# stm32f4discovery-daugherboard-v1-THT.net
KiCad netlist of a schematic drawn in EAGLE
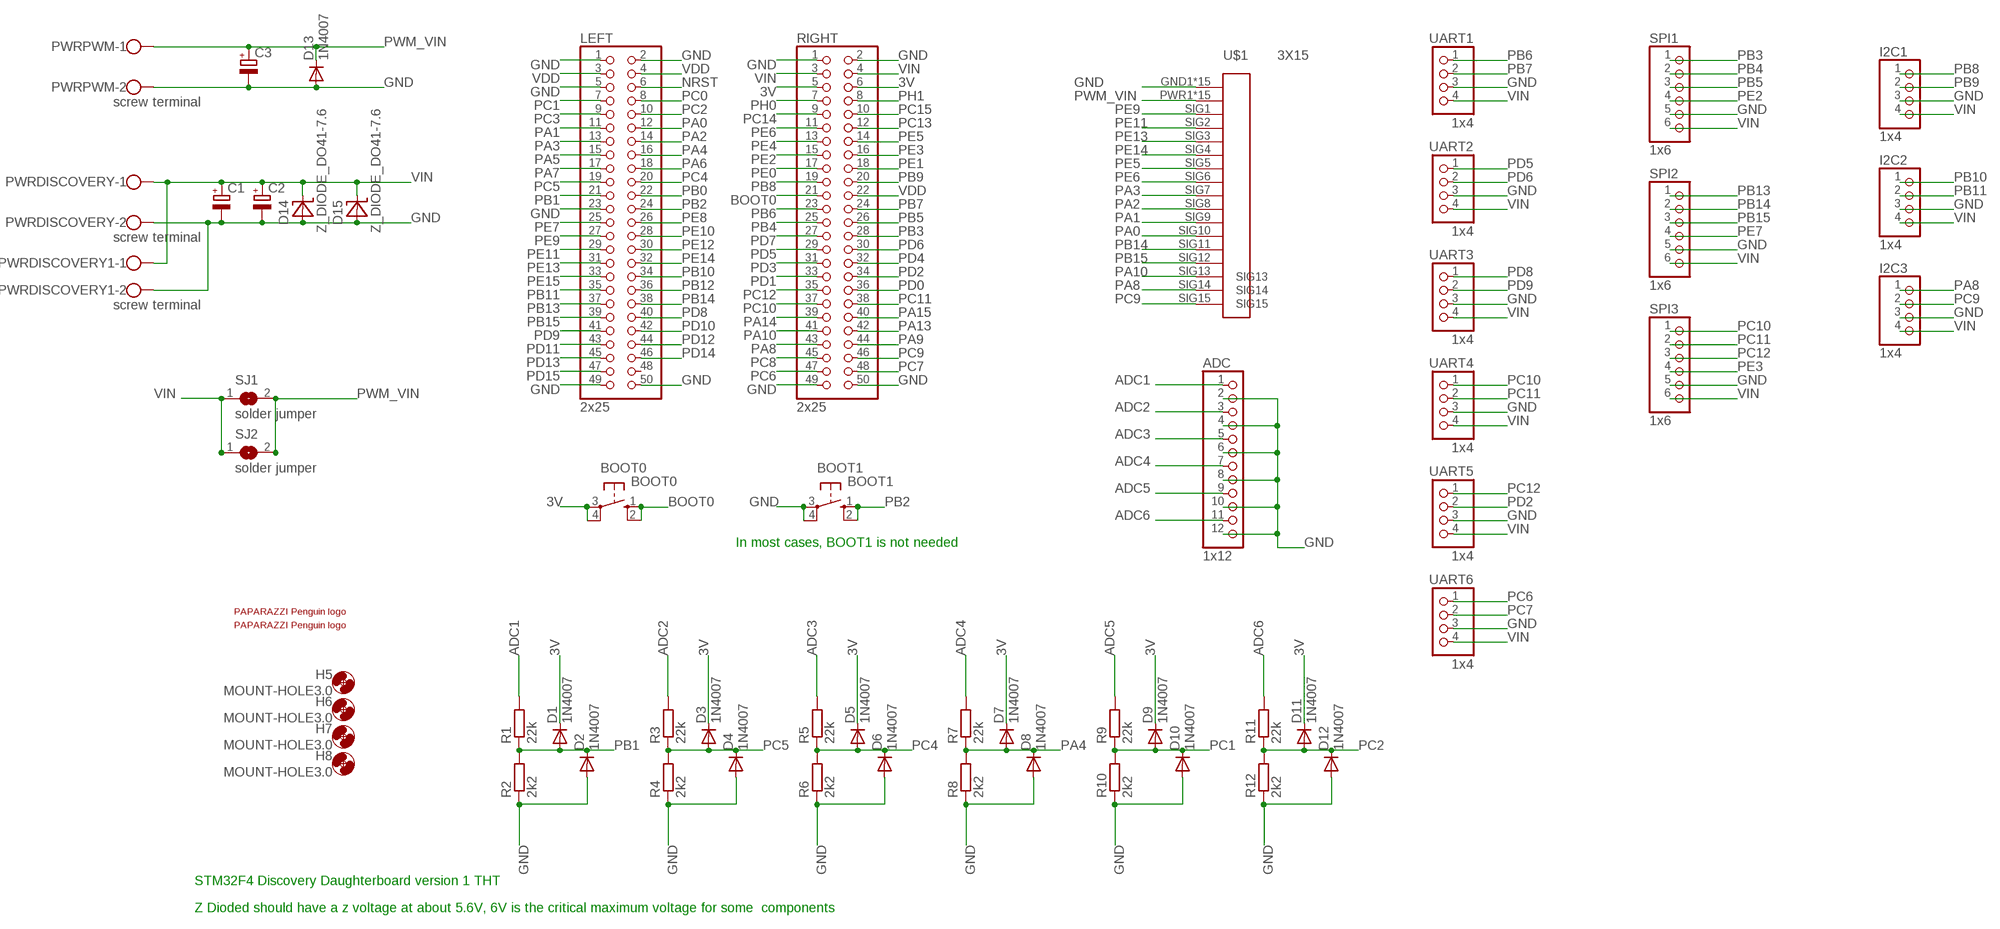
[diagram p0: schematic, sheet 1]

(export (version "E")
  (design (tool "Eeschema 10.0.6"))
  (components
    (comp (ref "ADC")
      (value "1x12")
      (footprint "eagle-import:1X12_90")
      (libsource (lib "eagle-import") (part "PINHD-1X12/90"))
    )
    (comp (ref "BOOT0")
      (value "BOOT0")
      (footprint "eagle-import:B3F-10XX")
      (fields (field (name "MPN") "B3F-1000"))
      (libsource (lib "eagle-import") (part "10-XX"))
    )
    (comp (ref "BOOT1")
      (value "BOOT1")
      (footprint "eagle-import:B3F-10XX")
      (fields (field (name "MPN") "B3F-1000"))
      (libsource (lib "eagle-import") (part "10-XX"))
    )
    (comp (ref "C1")
      (value "CPOL-EUE5-8.5")
      (footprint "eagle-import:E5-8,5")
      (libsource (lib "eagle-import") (part "CPOL-EUE5-8.5"))
    )
    (comp (ref "C2")
      (value "CPOL-EUE5-8.5")
      (footprint "eagle-import:E5-8,5")
      (libsource (lib "eagle-import") (part "CPOL-EUE5-8.5"))
    )
    (comp (ref "C3")
      (value "CPOL-EUE5-8.5")
      (footprint "eagle-import:E5-8,5")
      (libsource (lib "eagle-import") (part "CPOL-EUE5-8.5"))
    )
    (comp (ref "D1")
      (value "1N4007")
      (footprint "eagle-import:DO41-7.6_2")
      (libsource (lib "eagle-import") (part "1N4007"))
    )
    (comp (ref "D2")
      (value "1N4007")
      (footprint "eagle-import:DO41-7.6_2")
      (libsource (lib "eagle-import") (part "1N4007"))
    )
    (comp (ref "D3")
      (value "1N4007")
      (footprint "eagle-import:DO41-7.6_2")
      (libsource (lib "eagle-import") (part "1N4007"))
    )
    (comp (ref "D4")
      (value "1N4007")
      (footprint "eagle-import:DO41-7.6_2")
      (libsource (lib "eagle-import") (part "1N4007"))
    )
    (comp (ref "D5")
      (value "1N4007")
      (footprint "eagle-import:DO41-7.6_2")
      (libsource (lib "eagle-import") (part "1N4007"))
    )
    (comp (ref "D6")
      (value "1N4007")
      (footprint "eagle-import:DO41-7.6_2")
      (libsource (lib "eagle-import") (part "1N4007"))
    )
    (comp (ref "D7")
      (value "1N4007")
      (footprint "eagle-import:DO41-7.6_2")
      (libsource (lib "eagle-import") (part "1N4007"))
    )
    (comp (ref "D8")
      (value "1N4007")
      (footprint "eagle-import:DO41-7.6_2")
      (libsource (lib "eagle-import") (part "1N4007"))
    )
    (comp (ref "D9")
      (value "1N4007")
      (footprint "eagle-import:DO41-7.6_2")
      (libsource (lib "eagle-import") (part "1N4007"))
    )
    (comp (ref "D10")
      (value "1N4007")
      (footprint "eagle-import:DO41-7.6_2")
      (libsource (lib "eagle-import") (part "1N4007"))
    )
    (comp (ref "D11")
      (value "1N4007")
      (footprint "eagle-import:DO41-7.6_2")
      (libsource (lib "eagle-import") (part "1N4007"))
    )
    (comp (ref "D12")
      (value "1N4007")
      (footprint "eagle-import:DO41-7.6_2")
      (libsource (lib "eagle-import") (part "1N4007"))
    )
    (comp (ref "D13")
      (value "1N4007")
      (footprint "eagle-import:DO41-7.6_2")
      (libsource (lib "eagle-import") (part "1N4007"))
    )
    (comp (ref "D14")
      (value "Z_DIODE_DO41-7.6")
      (footprint "eagle-import:DO41-7.6_Z")
      (libsource (lib "eagle-import") (part "Z_DIODE_DO41-7.6"))
    )
    (comp (ref "D15")
      (value "Z_DIODE_DO41-7.6")
      (footprint "eagle-import:DO41-7.6_Z")
      (libsource (lib "eagle-import") (part "Z_DIODE_DO41-7.6"))
    )
    (comp (ref "H5")
      (value "MOUNT-HOLE3.0")
      (footprint "eagle-import:3,0")
      (libsource (lib "eagle-import") (part "MOUNT-HOLE3.0"))
    )
    (comp (ref "H6")
      (value "MOUNT-HOLE3.0")
      (footprint "eagle-import:3,0")
      (libsource (lib "eagle-import") (part "MOUNT-HOLE3.0"))
    )
    (comp (ref "H7")
      (value "MOUNT-HOLE3.0")
      (footprint "eagle-import:3,0")
      (libsource (lib "eagle-import") (part "MOUNT-HOLE3.0"))
    )
    (comp (ref "H8")
      (value "MOUNT-HOLE3.0")
      (footprint "eagle-import:3,0")
      (libsource (lib "eagle-import") (part "MOUNT-HOLE3.0"))
    )
    (comp (ref "I2C1")
      (value "1x4")
      (footprint "eagle-import:1X04_90")
      (libsource (lib "eagle-import") (part "PINHD-1X4/90"))
    )
    (comp (ref "I2C2")
      (value "1x4")
      (footprint "eagle-import:1X04_90")
      (libsource (lib "eagle-import") (part "PINHD-1X4/90"))
    )
    (comp (ref "I2C3")
      (value "1x4")
      (footprint "eagle-import:1X04_90")
      (libsource (lib "eagle-import") (part "PINHD-1X4/90"))
    )
    (comp (ref "LEFT")
      (value "2x25")
      (footprint "eagle-import:2X25")
      (libsource (lib "eagle-import") (part "PINHD-2X25"))
    )
    (comp (ref "PWRDISCOVERY")
      (value "screw terminal")
      (footprint "eagle-import:W237-102")
      (fields (field (name "MPN") "237-102"))
      (libsource (lib "eagle-import") (part "W237-102"))
    )
    (comp (ref "PWRDISCOVERY1")
      (value "screw terminal")
      (footprint "eagle-import:W237-102")
      (fields
        (field (name "MPN") "237-102")
        (field (name "MPN_1") "237-102")
        (field (name "OC_FARNELL") "unknown")
        (field (name "OC_NEWARK") "70K9898")
      )
      (libsource (lib "eagle-import") (part "W237-102"))
    )
    (comp (ref "PWRPWM")
      (value "screw terminal")
      (footprint "eagle-import:W237-102")
      (fields (field (name "MPN") "237-102"))
      (libsource (lib "eagle-import") (part "W237-102"))
    )
    (comp (ref "R1")
      (value "22k")
      (footprint "eagle-import:0204_7")
      (libsource (lib "eagle-import") (part "R-EU_0204/7"))
    )
    (comp (ref "R2")
      (value "2k2")
      (footprint "eagle-import:0204_7")
      (libsource (lib "eagle-import") (part "R-EU_0204/7"))
    )
    (comp (ref "R3")
      (value "22k")
      (footprint "eagle-import:0204_7")
      (libsource (lib "eagle-import") (part "R-EU_0204/7"))
    )
    (comp (ref "R4")
      (value "2k2")
      (footprint "eagle-import:0204_7")
      (libsource (lib "eagle-import") (part "R-EU_0204/7"))
    )
    (comp (ref "R5")
      (value "22k")
      (footprint "eagle-import:0204_7")
      (libsource (lib "eagle-import") (part "R-EU_0204/7"))
    )
    (comp (ref "R6")
      (value "2k2")
      (footprint "eagle-import:0204_7")
      (libsource (lib "eagle-import") (part "R-EU_0204/7"))
    )
    (comp (ref "R7")
      (value "22k")
      (footprint "eagle-import:0204_7")
      (libsource (lib "eagle-import") (part "R-EU_0204/7"))
    )
    (comp (ref "R8")
      (value "2k2")
      (footprint "eagle-import:0204_7")
      (libsource (lib "eagle-import") (part "R-EU_0204/7"))
    )
    (comp (ref "R9")
      (value "22k")
      (footprint "eagle-import:0204_7")
      (libsource (lib "eagle-import") (part "R-EU_0204/7"))
    )
    (comp (ref "R10")
      (value "2k2")
      (footprint "eagle-import:0204_7")
      (libsource (lib "eagle-import") (part "R-EU_0204/7"))
    )
    (comp (ref "R11")
      (value "22k")
      (footprint "eagle-import:0204_7")
      (libsource (lib "eagle-import") (part "R-EU_0204/7"))
    )
    (comp (ref "R12")
      (value "2k2")
      (footprint "eagle-import:0204_7")
      (libsource (lib "eagle-import") (part "R-EU_0204/7"))
    )
    (comp (ref "RIGHT")
      (value "2x25")
      (footprint "eagle-import:2X25")
      (libsource (lib "eagle-import") (part "PINHD-2X25"))
    )
    (comp (ref "SJ1")
      (value "solder jumper")
      (footprint "eagle-import:SJW")
      (libsource (lib "eagle-import") (part "SJW"))
    )
    (comp (ref "SJ2")
      (value "solder jumper")
      (footprint "eagle-import:SJW")
      (libsource (lib "eagle-import") (part "SJW"))
    )
    (comp (ref "SPI1")
      (value "1x6")
      (footprint "eagle-import:1X06_90")
      (libsource (lib "eagle-import") (part "PINHD-1X6/90"))
    )
    (comp (ref "SPI2")
      (value "1x6")
      (footprint "eagle-import:1X06_90")
      (libsource (lib "eagle-import") (part "PINHD-1X6/90"))
    )
    (comp (ref "SPI3")
      (value "1x6")
      (footprint "eagle-import:1X06_90")
      (libsource (lib "eagle-import") (part "PINHD-1X6/90"))
    )
    (comp (ref "U$1")
      (value "3X15")
      (footprint "eagle-import:3X15")
      (libsource (lib "eagle-import") (part "3X15"))
    )
    (comp (ref "U$2")
      (value "PAPARAZZI")
      (footprint "eagle-import:PAPARAZZI")
      (libsource (lib "eagle-import") (part "PAPARAZZI"))
    )
    (comp (ref "U$4")
      (value "üAüARAZZI_1400")
      (footprint "eagle-import:PAPARAZZI_1400")
      (libsource (lib "eagle-import") (part "üAüARAZZI_1400"))
    )
    (comp (ref "UART1")
      (value "1x4")
      (footprint "eagle-import:1X04_90")
      (libsource (lib "eagle-import") (part "PINHD-1X4/90"))
    )
    (comp (ref "UART2")
      (value "1x4")
      (footprint "eagle-import:1X04_90")
      (libsource (lib "eagle-import") (part "PINHD-1X4/90"))
    )
    (comp (ref "UART3")
      (value "1x4")
      (footprint "eagle-import:1X04_90")
      (libsource (lib "eagle-import") (part "PINHD-1X4/90"))
    )
    (comp (ref "UART4")
      (value "1x4")
      (footprint "eagle-import:1X04_90")
      (libsource (lib "eagle-import") (part "PINHD-1X4/90"))
    )
    (comp (ref "UART5")
      (value "1x4")
      (footprint "eagle-import:1X04_90")
      (libsource (lib "eagle-import") (part "PINHD-1X4/90"))
    )
    (comp (ref "UART6")
      (value "1x4")
      (footprint "eagle-import:1X04_90")
      (libsource (lib "eagle-import") (part "PINHD-1X4/90"))
    )
  )
  (nets
    (net (code "1") (name "/3V") (class "Default")
      (node (ref "BOOT0") (pin "3") (pinfunction "P_3") (pintype "passive"))
      (node (ref "BOOT0") (pin "4") (pinfunction "P1_4") (pintype "passive"))
      (node (ref "D1") (pin "C") (pinfunction "C_C") (pintype "passive"))
      (node (ref "D11") (pin "C") (pinfunction "C_C") (pintype "passive"))
      (node (ref "D3") (pin "C") (pinfunction "C_C") (pintype "passive"))
      (node (ref "D5") (pin "C") (pinfunction "C_C") (pintype "passive"))
      (node (ref "D7") (pin "C") (pinfunction "C_C") (pintype "passive"))
      (node (ref "D9") (pin "C") (pinfunction "C_C") (pintype "passive"))
      (node (ref "RIGHT") (pin "5") (pinfunction "5_5") (pintype "passive"))
      (node (ref "RIGHT") (pin "6") (pinfunction "6_6") (pintype "passive"))
    )
    (net (code "2") (name "/ADC1") (class "Default")
      (node (ref "ADC") (pin "1") (pinfunction "1_1") (pintype "passive"))
      (node (ref "R1") (pin "2") (pinfunction "2_2") (pintype "passive"))
    )
    (net (code "3") (name "/ADC2") (class "Default")
      (node (ref "ADC") (pin "3") (pinfunction "3_3") (pintype "passive"))
      (node (ref "R3") (pin "2") (pinfunction "2_2") (pintype "passive"))
    )
    (net (code "4") (name "/ADC3") (class "Default")
      (node (ref "ADC") (pin "5") (pinfunction "5_5") (pintype "passive"))
      (node (ref "R5") (pin "2") (pinfunction "2_2") (pintype "passive"))
    )
    (net (code "5") (name "/ADC4") (class "Default")
      (node (ref "ADC") (pin "7") (pinfunction "7_7") (pintype "passive"))
      (node (ref "R7") (pin "2") (pinfunction "2_2") (pintype "passive"))
    )
    (net (code "6") (name "/ADC5") (class "Default")
      (node (ref "ADC") (pin "9") (pinfunction "9_9") (pintype "passive"))
      (node (ref "R9") (pin "2") (pinfunction "2_2") (pintype "passive"))
    )
    (net (code "7") (name "/ADC6") (class "Default")
      (node (ref "ADC") (pin "11") (pinfunction "11_11") (pintype "passive"))
      (node (ref "R11") (pin "2") (pinfunction "2_2") (pintype "passive"))
    )
    (net (code "8") (name "/BOOT0") (class "Default")
      (node (ref "BOOT0") (pin "1") (pinfunction "S_1") (pintype "passive"))
      (node (ref "BOOT0") (pin "2") (pinfunction "S1_2") (pintype "passive"))
      (node (ref "RIGHT") (pin "21") (pinfunction "21_21") (pintype "passive"))
    )
    (net (code "9") (name "/GND") (class "Default")
      (node (ref "ADC") (pin "10") (pinfunction "10_10") (pintype "passive"))
      (node (ref "ADC") (pin "12") (pinfunction "12_12") (pintype "passive"))
      (node (ref "ADC") (pin "2") (pinfunction "2_2") (pintype "passive"))
      (node (ref "ADC") (pin "4") (pinfunction "4_4") (pintype "passive"))
      (node (ref "ADC") (pin "6") (pinfunction "6_6") (pintype "passive"))
      (node (ref "ADC") (pin "8") (pinfunction "8_8") (pintype "passive"))
      (node (ref "BOOT1") (pin "3") (pinfunction "P_3") (pintype "passive"))
      (node (ref "BOOT1") (pin "4") (pinfunction "P1_4") (pintype "passive"))
      (node (ref "C1") (pin "-") (pinfunction "-_-") (pintype "passive"))
      (node (ref "C2") (pin "-") (pinfunction "-_-") (pintype "passive"))
      (node (ref "C3") (pin "-") (pinfunction "-_-") (pintype "passive"))
      (node (ref "D10") (pin "A") (pinfunction "A_A") (pintype "passive"))
      (node (ref "D12") (pin "A") (pinfunction "A_A") (pintype "passive"))
      (node (ref "D13") (pin "A") (pinfunction "A_A") (pintype "passive"))
      (node (ref "D14") (pin "A") (pinfunction "A_A") (pintype "passive"))
      (node (ref "D15") (pin "A") (pinfunction "A_A") (pintype "passive"))
      (node (ref "D2") (pin "A") (pinfunction "A_A") (pintype "passive"))
      (node (ref "D4") (pin "A") (pinfunction "A_A") (pintype "passive"))
      (node (ref "D6") (pin "A") (pinfunction "A_A") (pintype "passive"))
      (node (ref "D8") (pin "A") (pinfunction "A_A") (pintype "passive"))
      (node (ref "I2C1") (pin "3") (pinfunction "3_3") (pintype "passive"))
      (node (ref "I2C2") (pin "3") (pinfunction "3_3") (pintype "passive"))
      (node (ref "I2C3") (pin "3") (pinfunction "3_3") (pintype "passive"))
      (node (ref "LEFT") (pin "1") (pinfunction "1_1") (pintype "passive"))
      (node (ref "LEFT") (pin "2") (pinfunction "2_2") (pintype "passive"))
      (node (ref "LEFT") (pin "23") (pinfunction "23_23") (pintype "passive"))
      (node (ref "LEFT") (pin "49") (pinfunction "49_49") (pintype "passive"))
      (node (ref "LEFT") (pin "5") (pinfunction "5_5") (pintype "passive"))
      (node (ref "LEFT") (pin "50") (pinfunction "50_50") (pintype "passive"))
      (node (ref "PWRDISCOVERY") (pin "2") (pinfunction "KL_2") (pintype "passive"))
      (node (ref "PWRDISCOVERY1") (pin "2") (pinfunction "KL_2") (pintype "passive"))
      (node (ref "PWRPWM") (pin "2") (pinfunction "KL_2") (pintype "passive"))
      (node (ref "R10") (pin "1") (pinfunction "1_1") (pintype "passive"))
      (node (ref "R12") (pin "1") (pinfunction "1_1") (pintype "passive"))
      (node (ref "R2") (pin "1") (pinfunction "1_1") (pintype "passive"))
      (node (ref "R4") (pin "1") (pinfunction "1_1") (pintype "passive"))
      (node (ref "R6") (pin "1") (pinfunction "1_1") (pintype "passive"))
      (node (ref "R8") (pin "1") (pinfunction "1_1") (pintype "passive"))
      (node (ref "RIGHT") (pin "1") (pinfunction "1_1") (pintype "passive"))
      (node (ref "RIGHT") (pin "2") (pinfunction "2_2") (pintype "passive"))
      (node (ref "RIGHT") (pin "49") (pinfunction "49_49") (pintype "passive"))
      (node (ref "RIGHT") (pin "50") (pinfunction "50_50") (pintype "passive"))
      (node (ref "SPI1") (pin "5") (pinfunction "5_5") (pintype "passive"))
      (node (ref "SPI2") (pin "5") (pinfunction "5_5") (pintype "passive"))
      (node (ref "SPI3") (pin "5") (pinfunction "5_5") (pintype "passive"))
      (node (ref "U$1") (pin "GND1") (pinfunction "GND_GND1") (pintype "bidirectional"))
      (node (ref "U$1") (pin "GND10") (pinfunction "GND_GND10") (pintype "bidirectional"))
      (node (ref "U$1") (pin "GND11") (pinfunction "GND_GND11") (pintype "bidirectional"))
      (node (ref "U$1") (pin "GND12") (pinfunction "GND_GND12") (pintype "bidirectional"))
      (node (ref "U$1") (pin "GND13") (pinfunction "GND_GND13") (pintype "bidirectional"))
      (node (ref "U$1") (pin "GND14") (pinfunction "GND_GND14") (pintype "bidirectional"))
      (node (ref "U$1") (pin "GND15") (pinfunction "GND_GND15") (pintype "bidirectional"))
      (node (ref "U$1") (pin "GND2") (pinfunction "GND_GND2") (pintype "bidirectional"))
      (node (ref "U$1") (pin "GND3") (pinfunction "GND_GND3") (pintype "bidirectional"))
      (node (ref "U$1") (pin "GND4") (pinfunction "GND_GND4") (pintype "bidirectional"))
      (node (ref "U$1") (pin "GND5") (pinfunction "GND_GND5") (pintype "bidirectional"))
      (node (ref "U$1") (pin "GND6") (pinfunction "GND_GND6") (pintype "bidirectional"))
      (node (ref "U$1") (pin "GND7") (pinfunction "GND_GND7") (pintype "bidirectional"))
      (node (ref "U$1") (pin "GND8") (pinfunction "GND_GND8") (pintype "bidirectional"))
      (node (ref "U$1") (pin "GND9") (pinfunction "GND_GND9") (pintype "bidirectional"))
      (node (ref "UART1") (pin "3") (pinfunction "3_3") (pintype "passive"))
      (node (ref "UART2") (pin "3") (pinfunction "3_3") (pintype "passive"))
      (node (ref "UART3") (pin "3") (pinfunction "3_3") (pintype "passive"))
      (node (ref "UART4") (pin "3") (pinfunction "3_3") (pintype "passive"))
      (node (ref "UART5") (pin "3") (pinfunction "3_3") (pintype "passive"))
      (node (ref "UART6") (pin "3") (pinfunction "3_3") (pintype "passive"))
    )
    (net (code "10") (name "/NRST") (class "Default")
      (node (ref "LEFT") (pin "6") (pinfunction "6_6") (pintype "passive"))
    )
    (net (code "11") (name "/PA0") (class "Default")
      (node (ref "LEFT") (pin "12") (pinfunction "12_12") (pintype "passive"))
      (node (ref "U$1") (pin "SIG10") (pinfunction "SIG10_SIG10") (pintype "bidirectional"))
    )
    (net (code "12") (name "/PA1") (class "Default")
      (node (ref "LEFT") (pin "11") (pinfunction "11_11") (pintype "passive"))
      (node (ref "U$1") (pin "SIG9") (pinfunction "SIG9_SIG9") (pintype "bidirectional"))
    )
    (net (code "13") (name "/PA2") (class "Default")
      (node (ref "LEFT") (pin "14") (pinfunction "14_14") (pintype "passive"))
      (node (ref "U$1") (pin "SIG8") (pinfunction "SIG8_SIG8") (pintype "bidirectional"))
    )
    (net (code "14") (name "/PA3") (class "Default")
      (node (ref "LEFT") (pin "13") (pinfunction "13_13") (pintype "passive"))
      (node (ref "U$1") (pin "SIG7") (pinfunction "SIG7_SIG7") (pintype "bidirectional"))
    )
    (net (code "15") (name "/PA4") (class "Default")
      (node (ref "D7") (pin "A") (pinfunction "A_A") (pintype "passive"))
      (node (ref "D8") (pin "C") (pinfunction "C_C") (pintype "passive"))
      (node (ref "LEFT") (pin "16") (pinfunction "16_16") (pintype "passive"))
      (node (ref "R7") (pin "1") (pinfunction "1_1") (pintype "passive"))
      (node (ref "R8") (pin "2") (pinfunction "2_2") (pintype "passive"))
    )
    (net (code "16") (name "/PA5") (class "Default")
      (node (ref "LEFT") (pin "15") (pinfunction "15_15") (pintype "passive"))
    )
    (net (code "17") (name "/PA6") (class "Default")
      (node (ref "LEFT") (pin "18") (pinfunction "18_18") (pintype "passive"))
    )
    (net (code "18") (name "/PA7") (class "Default")
      (node (ref "LEFT") (pin "17") (pinfunction "17_17") (pintype "passive"))
    )
    (net (code "19") (name "/PA8") (class "Default")
      (node (ref "I2C3") (pin "1") (pinfunction "1_1") (pintype "passive"))
      (node (ref "RIGHT") (pin "43") (pinfunction "43_43") (pintype "passive"))
      (node (ref "U$1") (pin "SIG14") (pinfunction "SIG14_SIG14") (pintype "bidirectional"))
    )
    (net (code "20") (name "/PA9") (class "Default")
      (node (ref "RIGHT") (pin "44") (pinfunction "44_44") (pintype "passive"))
    )
    (net (code "21") (name "/PA10") (class "Default")
      (node (ref "RIGHT") (pin "41") (pinfunction "41_41") (pintype "passive"))
      (node (ref "U$1") (pin "SIG13") (pinfunction "SIG13_SIG13") (pintype "bidirectional"))
    )
    (net (code "22") (name "/PA13") (class "Default")
      (node (ref "RIGHT") (pin "42") (pinfunction "42_42") (pintype "passive"))
    )
    (net (code "23") (name "/PA14") (class "Default")
      (node (ref "RIGHT") (pin "39") (pinfunction "39_39") (pintype "passive"))
    )
    (net (code "24") (name "/PA15") (class "Default")
      (node (ref "RIGHT") (pin "40") (pinfunction "40_40") (pintype "passive"))
    )
    (net (code "25") (name "/PB0") (class "Default")
      (node (ref "LEFT") (pin "22") (pinfunction "22_22") (pintype "passive"))
    )
    (net (code "26") (name "/PB1") (class "Default")
      (node (ref "D1") (pin "A") (pinfunction "A_A") (pintype "passive"))
      (node (ref "D2") (pin "C") (pinfunction "C_C") (pintype "passive"))
      (node (ref "LEFT") (pin "21") (pinfunction "21_21") (pintype "passive"))
      (node (ref "R1") (pin "1") (pinfunction "1_1") (pintype "passive"))
      (node (ref "R2") (pin "2") (pinfunction "2_2") (pintype "passive"))
    )
    (net (code "27") (name "/PB2") (class "Default")
      (node (ref "BOOT1") (pin "1") (pinfunction "S_1") (pintype "passive"))
      (node (ref "BOOT1") (pin "2") (pinfunction "S1_2") (pintype "passive"))
      (node (ref "LEFT") (pin "24") (pinfunction "24_24") (pintype "passive"))
    )
    (net (code "28") (name "/PB3") (class "Default")
      (node (ref "RIGHT") (pin "28") (pinfunction "28_28") (pintype "passive"))
      (node (ref "SPI1") (pin "1") (pinfunction "1_1") (pintype "passive"))
    )
    (net (code "29") (name "/PB4") (class "Default")
      (node (ref "RIGHT") (pin "25") (pinfunction "25_25") (pintype "passive"))
      (node (ref "SPI1") (pin "2") (pinfunction "2_2") (pintype "passive"))
    )
    (net (code "30") (name "/PB5") (class "Default")
      (node (ref "RIGHT") (pin "26") (pinfunction "26_26") (pintype "passive"))
      (node (ref "SPI1") (pin "3") (pinfunction "3_3") (pintype "passive"))
    )
    (net (code "31") (name "/PB6") (class "Default")
      (node (ref "RIGHT") (pin "23") (pinfunction "23_23") (pintype "passive"))
      (node (ref "UART1") (pin "1") (pinfunction "1_1") (pintype "passive"))
    )
    (net (code "32") (name "/PB7") (class "Default")
      (node (ref "RIGHT") (pin "24") (pinfunction "24_24") (pintype "passive"))
      (node (ref "UART1") (pin "2") (pinfunction "2_2") (pintype "passive"))
    )
    (net (code "33") (name "/PB8") (class "Default")
      (node (ref "I2C1") (pin "1") (pinfunction "1_1") (pintype "passive"))
      (node (ref "RIGHT") (pin "19") (pinfunction "19_19") (pintype "passive"))
    )
    (net (code "34") (name "/PB9") (class "Default")
      (node (ref "I2C1") (pin "2") (pinfunction "2_2") (pintype "passive"))
      (node (ref "RIGHT") (pin "20") (pinfunction "20_20") (pintype "passive"))
    )
    (net (code "35") (name "/PB10") (class "Default")
      (node (ref "I2C2") (pin "1") (pinfunction "1_1") (pintype "passive"))
      (node (ref "LEFT") (pin "34") (pinfunction "34_34") (pintype "passive"))
    )
    (net (code "36") (name "/PB11") (class "Default")
      (node (ref "I2C2") (pin "2") (pinfunction "2_2") (pintype "passive"))
      (node (ref "LEFT") (pin "35") (pinfunction "35_35") (pintype "passive"))
    )
    (net (code "37") (name "/PB12") (class "Default")
      (node (ref "LEFT") (pin "36") (pinfunction "36_36") (pintype "passive"))
    )
    (net (code "38") (name "/PB13") (class "Default")
      (node (ref "LEFT") (pin "37") (pinfunction "37_37") (pintype "passive"))
      (node (ref "SPI2") (pin "1") (pinfunction "1_1") (pintype "passive"))
    )
    (net (code "39") (name "/PB14") (class "Default")
      (node (ref "LEFT") (pin "38") (pinfunction "38_38") (pintype "passive"))
      (node (ref "SPI2") (pin "2") (pinfunction "2_2") (pintype "passive"))
      (node (ref "U$1") (pin "SIG11") (pinfunction "SIG11_SIG11") (pintype "bidirectional"))
    )
    (net (code "40") (name "/PB15") (class "Default")
      (node (ref "LEFT") (pin "39") (pinfunction "39_39") (pintype "passive"))
      (node (ref "SPI2") (pin "3") (pinfunction "3_3") (pintype "passive"))
      (node (ref "U$1") (pin "SIG12") (pinfunction "SIG12_SIG12") (pintype "bidirectional"))
    )
    (net (code "41") (name "/PC0") (class "Default")
      (node (ref "LEFT") (pin "8") (pinfunction "8_8") (pintype "passive"))
    )
    (net (code "42") (name "/PC1") (class "Default")
      (node (ref "D10") (pin "C") (pinfunction "C_C") (pintype "passive"))
      (node (ref "D9") (pin "A") (pinfunction "A_A") (pintype "passive"))
      (node (ref "LEFT") (pin "7") (pinfunction "7_7") (pintype "passive"))
      (node (ref "R10") (pin "2") (pinfunction "2_2") (pintype "passive"))
      (node (ref "R9") (pin "1") (pinfunction "1_1") (pintype "passive"))
    )
    (net (code "43") (name "/PC2") (class "Default")
      (node (ref "D11") (pin "A") (pinfunction "A_A") (pintype "passive"))
      (node (ref "D12") (pin "C") (pinfunction "C_C") (pintype "passive"))
      (node (ref "LEFT") (pin "10") (pinfunction "10_10") (pintype "passive"))
      (node (ref "R11") (pin "1") (pinfunction "1_1") (pintype "passive"))
      (node (ref "R12") (pin "2") (pinfunction "2_2") (pintype "passive"))
    )
    (net (code "44") (name "/PC3") (class "Default")
      (node (ref "LEFT") (pin "9") (pinfunction "9_9") (pintype "passive"))
    )
    (net (code "45") (name "/PC4") (class "Default")
      (node (ref "D5") (pin "A") (pinfunction "A_A") (pintype "passive"))
      (node (ref "D6") (pin "C") (pinfunction "C_C") (pintype "passive"))
      (node (ref "LEFT") (pin "20") (pinfunction "20_20") (pintype "passive"))
      (node (ref "R5") (pin "1") (pinfunction "1_1") (pintype "passive"))
      (node (ref "R6") (pin "2") (pinfunction "2_2") (pintype "passive"))
    )
    (net (code "46") (name "/PC5") (class "Default")
      (node (ref "D3") (pin "A") (pinfunction "A_A") (pintype "passive"))
      (node (ref "D4") (pin "C") (pinfunction "C_C") (pintype "passive"))
      (node (ref "LEFT") (pin "19") (pinfunction "19_19") (pintype "passive"))
      (node (ref "R3") (pin "1") (pinfunction "1_1") (pintype "passive"))
      (node (ref "R4") (pin "2") (pinfunction "2_2") (pintype "passive"))
    )
    (net (code "47") (name "/PC6") (class "Default")
      (node (ref "RIGHT") (pin "47") (pinfunction "47_47") (pintype "passive"))
      (node (ref "UART6") (pin "1") (pinfunction "1_1") (pintype "passive"))
    )
    (net (code "48") (name "/PC7") (class "Default")
      (node (ref "RIGHT") (pin "48") (pinfunction "48_48") (pintype "passive"))
      (node (ref "UART6") (pin "2") (pinfunction "2_2") (pintype "passive"))
    )
    (net (code "49") (name "/PC8") (class "Default")
      (node (ref "RIGHT") (pin "45") (pinfunction "45_45") (pintype "passive"))
    )
    (net (code "50") (name "/PC9") (class "Default")
      (node (ref "I2C3") (pin "2") (pinfunction "2_2") (pintype "passive"))
      (node (ref "RIGHT") (pin "46") (pinfunction "46_46") (pintype "passive"))
      (node (ref "U$1") (pin "SIG15") (pinfunction "SIG15_SIG15") (pintype "bidirectional"))
    )
    (net (code "51") (name "/PC10") (class "Default")
      (node (ref "RIGHT") (pin "37") (pinfunction "37_37") (pintype "passive"))
      (node (ref "SPI3") (pin "1") (pinfunction "1_1") (pintype "passive"))
      (node (ref "UART4") (pin "1") (pinfunction "1_1") (pintype "passive"))
    )
    (net (code "52") (name "/PC11") (class "Default")
      (node (ref "RIGHT") (pin "38") (pinfunction "38_38") (pintype "passive"))
      (node (ref "SPI3") (pin "2") (pinfunction "2_2") (pintype "passive"))
      (node (ref "UART4") (pin "2") (pinfunction "2_2") (pintype "passive"))
    )
    (net (code "53") (name "/PC12") (class "Default")
      (node (ref "RIGHT") (pin "35") (pinfunction "35_35") (pintype "passive"))
      (node (ref "SPI3") (pin "3") (pinfunction "3_3") (pintype "passive"))
      (node (ref "UART5") (pin "1") (pinfunction "1_1") (pintype "passive"))
    )
    (net (code "54") (name "/PC13") (class "Default")
      (node (ref "RIGHT") (pin "12") (pinfunction "12_12") (pintype "passive"))
    )
    (net (code "55") (name "/PC14") (class "Default")
      (node (ref "RIGHT") (pin "9") (pinfunction "9_9") (pintype "passive"))
    )
    (net (code "56") (name "/PC15") (class "Default")
      (node (ref "RIGHT") (pin "10") (pinfunction "10_10") (pintype "passive"))
    )
    (net (code "57") (name "/PD0") (class "Default")
      (node (ref "RIGHT") (pin "36") (pinfunction "36_36") (pintype "passive"))
    )
    (net (code "58") (name "/PD1") (class "Default")
      (node (ref "RIGHT") (pin "33") (pinfunction "33_33") (pintype "passive"))
    )
    (net (code "59") (name "/PD2") (class "Default")
      (node (ref "RIGHT") (pin "34") (pinfunction "34_34") (pintype "passive"))
      (node (ref "UART5") (pin "2") (pinfunction "2_2") (pintype "passive"))
    )
    (net (code "60") (name "/PD3") (class "Default")
      (node (ref "RIGHT") (pin "31") (pinfunction "31_31") (pintype "passive"))
    )
    (net (code "61") (name "/PD4") (class "Default")
      (node (ref "RIGHT") (pin "32") (pinfunction "32_32") (pintype "passive"))
    )
    (net (code "62") (name "/PD5") (class "Default")
      (node (ref "RIGHT") (pin "29") (pinfunction "29_29") (pintype "passive"))
      (node (ref "UART2") (pin "1") (pinfunction "1_1") (pintype "passive"))
    )
    (net (code "63") (name "/PD6") (class "Default")
      (node (ref "RIGHT") (pin "30") (pinfunction "30_30") (pintype "passive"))
      (node (ref "UART2") (pin "2") (pinfunction "2_2") (pintype "passive"))
    )
    (net (code "64") (name "/PD7") (class "Default")
      (node (ref "RIGHT") (pin "27") (pinfunction "27_27") (pintype "passive"))
    )
    (net (code "65") (name "/PD8") (class "Default")
      (node (ref "LEFT") (pin "40") (pinfunction "40_40") (pintype "passive"))
      (node (ref "UART3") (pin "1") (pinfunction "1_1") (pintype "passive"))
    )
    (net (code "66") (name "/PD9") (class "Default")
      (node (ref "LEFT") (pin "41") (pinfunction "41_41") (pintype "passive"))
      (node (ref "UART3") (pin "2") (pinfunction "2_2") (pintype "passive"))
    )
    (net (code "67") (name "/PD10") (class "Default")
      (node (ref "LEFT") (pin "42") (pinfunction "42_42") (pintype "passive"))
    )
    (net (code "68") (name "/PD11") (class "Default")
      (node (ref "LEFT") (pin "43") (pinfunction "43_43") (pintype "passive"))
    )
    (net (code "69") (name "/PD12") (class "Default")
      (node (ref "LEFT") (pin "44") (pinfunction "44_44") (pintype "passive"))
    )
    (net (code "70") (name "/PD13") (class "Default")
      (node (ref "LEFT") (pin "45") (pinfunction "45_45") (pintype "passive"))
    )
    (net (code "71") (name "/PD14") (class "Default")
      (node (ref "LEFT") (pin "46") (pinfunction "46_46") (pintype "passive"))
    )
    (net (code "72") (name "/PD15") (class "Default")
      (node (ref "LEFT") (pin "47") (pinfunction "47_47") (pintype "passive"))
    )
    (net (code "73") (name "/PE0") (class "Default")
      (node (ref "RIGHT") (pin "17") (pinfunction "17_17") (pintype "passive"))
    )
    (net (code "74") (name "/PE1") (class "Default")
      (node (ref "RIGHT") (pin "18") (pinfunction "18_18") (pintype "passive"))
    )
    (net (code "75") (name "/PE2") (class "Default")
      (node (ref "RIGHT") (pin "15") (pinfunction "15_15") (pintype "passive"))
      (node (ref "SPI1") (pin "4") (pinfunction "4_4") (pintype "passive"))
    )
    (net (code "76") (name "/PE3") (class "Default")
      (node (ref "RIGHT") (pin "16") (pinfunction "16_16") (pintype "passive"))
      (node (ref "SPI3") (pin "4") (pinfunction "4_4") (pintype "passive"))
    )
    (net (code "77") (name "/PE4") (class "Default")
      (node (ref "RIGHT") (pin "13") (pinfunction "13_13") (pintype "passive"))
    )
    (net (code "78") (name "/PE5") (class "Default")
      (node (ref "RIGHT") (pin "14") (pinfunction "14_14") (pintype "passive"))
      (node (ref "U$1") (pin "SIG5") (pinfunction "SIG5_SIG5") (pintype "bidirectional"))
    )
    (net (code "79") (name "/PE6") (class "Default")
      (node (ref "RIGHT") (pin "11") (pinfunction "11_11") (pintype "passive"))
      (node (ref "U$1") (pin "SIG6") (pinfunction "SIG6_SIG6") (pintype "bidirectional"))
    )
    (net (code "80") (name "/PE7") (class "Default")
      (node (ref "LEFT") (pin "25") (pinfunction "25_25") (pintype "passive"))
      (node (ref "SPI2") (pin "4") (pinfunction "4_4") (pintype "passive"))
    )
    (net (code "81") (name "/PE8") (class "Default")
      (node (ref "LEFT") (pin "26") (pinfunction "26_26") (pintype "passive"))
    )
    (net (code "82") (name "/PE9") (class "Default")
      (node (ref "LEFT") (pin "27") (pinfunction "27_27") (pintype "passive"))
      (node (ref "U$1") (pin "SIG1") (pinfunction "SIG1_SIG1") (pintype "bidirectional"))
    )
    (net (code "83") (name "/PE10") (class "Default")
      (node (ref "LEFT") (pin "28") (pinfunction "28_28") (pintype "passive"))
    )
    (net (code "84") (name "/PE11") (class "Default")
      (node (ref "LEFT") (pin "29") (pinfunction "29_29") (pintype "passive"))
      (node (ref "U$1") (pin "SIG2") (pinfunction "SIG2_SIG2") (pintype "bidirectional"))
    )
    (net (code "85") (name "/PE12") (class "Default")
      (node (ref "LEFT") (pin "30") (pinfunction "30_30") (pintype "passive"))
    )
    (net (code "86") (name "/PE13") (class "Default")
      (node (ref "LEFT") (pin "31") (pinfunction "31_31") (pintype "passive"))
      (node (ref "U$1") (pin "SIG3") (pinfunction "SIG3_SIG3") (pintype "bidirectional"))
    )
    (net (code "87") (name "/PE14") (class "Default")
      (node (ref "LEFT") (pin "32") (pinfunction "32_32") (pintype "passive"))
      (node (ref "U$1") (pin "SIG4") (pinfunction "SIG4_SIG4") (pintype "bidirectional"))
    )
    (net (code "88") (name "/PE15") (class "Default")
      (node (ref "LEFT") (pin "33") (pinfunction "33_33") (pintype "passive"))
    )
    (net (code "89") (name "/PH0") (class "Default")
      (node (ref "RIGHT") (pin "7") (pinfunction "7_7") (pintype "passive"))
    )
    (net (code "90") (name "/PH1") (class "Default")
      (node (ref "RIGHT") (pin "8") (pinfunction "8_8") (pintype "passive"))
    )
    (net (code "91") (name "/PWM_VIN") (class "Default")
      (node (ref "C3") (pin "+") (pinfunction "+_+") (pintype "passive"))
      (node (ref "D13") (pin "C") (pinfunction "C_C") (pintype "passive"))
      (node (ref "PWRPWM") (pin "1") (pinfunction "KL_1") (pintype "passive"))
      (node (ref "SJ1") (pin "2") (pinfunction "2_2") (pintype "passive"))
      (node (ref "SJ2") (pin "2") (pinfunction "2_2") (pintype "passive"))
      (node (ref "U$1") (pin "PWR1") (pinfunction "PWR_PWR1") (pintype "bidirectional"))
      (node (ref "U$1") (pin "PWR10") (pinfunction "PWR_PWR10") (pintype "bidirectional"))
      (node (ref "U$1") (pin "PWR11") (pinfunction "PWR_PWR11") (pintype "bidirectional"))
      (node (ref "U$1") (pin "PWR12") (pinfunction "PWR_PWR12") (pintype "bidirectional"))
      (node (ref "U$1") (pin "PWR13") (pinfunction "PWR_PWR13") (pintype "bidirectional"))
      (node (ref "U$1") (pin "PWR14") (pinfunction "PWR_PWR14") (pintype "bidirectional"))
      (node (ref "U$1") (pin "PWR15") (pinfunction "PWR_PWR15") (pintype "bidirectional"))
      (node (ref "U$1") (pin "PWR2") (pinfunction "PWR_PWR2") (pintype "bidirectional"))
      (node (ref "U$1") (pin "PWR3") (pinfunction "PWR_PWR3") (pintype "bidirectional"))
      (node (ref "U$1") (pin "PWR4") (pinfunction "PWR_PWR4") (pintype "bidirectional"))
      (node (ref "U$1") (pin "PWR5") (pinfunction "PWR_PWR5") (pintype "bidirectional"))
      (node (ref "U$1") (pin "PWR6") (pinfunction "PWR_PWR6") (pintype "bidirectional"))
      (node (ref "U$1") (pin "PWR7") (pinfunction "PWR_PWR7") (pintype "bidirectional"))
      (node (ref "U$1") (pin "PWR8") (pinfunction "PWR_PWR8") (pintype "bidirectional"))
      (node (ref "U$1") (pin "PWR9") (pinfunction "PWR_PWR9") (pintype "bidirectional"))
    )
    (net (code "92") (name "/VDD") (class "Default")
      (node (ref "LEFT") (pin "3") (pinfunction "3_3") (pintype "passive"))
      (node (ref "LEFT") (pin "4") (pinfunction "4_4") (pintype "passive"))
      (node (ref "RIGHT") (pin "22") (pinfunction "22_22") (pintype "passive"))
    )
    (net (code "93") (name "/VIN") (class "Default")
      (node (ref "C1") (pin "+") (pinfunction "+_+") (pintype "passive"))
      (node (ref "C2") (pin "+") (pinfunction "+_+") (pintype "passive"))
      (node (ref "D14") (pin "C") (pinfunction "C_C") (pintype "passive"))
      (node (ref "D15") (pin "C") (pinfunction "C_C") (pintype "passive"))
      (node (ref "I2C1") (pin "4") (pinfunction "4_4") (pintype "passive"))
      (node (ref "I2C2") (pin "4") (pinfunction "4_4") (pintype "passive"))
      (node (ref "I2C3") (pin "4") (pinfunction "4_4") (pintype "passive"))
      (node (ref "PWRDISCOVERY") (pin "1") (pinfunction "KL_1") (pintype "passive"))
      (node (ref "PWRDISCOVERY1") (pin "1") (pinfunction "KL_1") (pintype "passive"))
      (node (ref "RIGHT") (pin "3") (pinfunction "3_3") (pintype "passive"))
      (node (ref "RIGHT") (pin "4") (pinfunction "4_4") (pintype "passive"))
      (node (ref "SJ1") (pin "1") (pinfunction "1_1") (pintype "passive"))
      (node (ref "SJ2") (pin "1") (pinfunction "1_1") (pintype "passive"))
      (node (ref "SPI1") (pin "6") (pinfunction "6_6") (pintype "passive"))
      (node (ref "SPI2") (pin "6") (pinfunction "6_6") (pintype "passive"))
      (node (ref "SPI3") (pin "6") (pinfunction "6_6") (pintype "passive"))
      (node (ref "UART1") (pin "4") (pinfunction "4_4") (pintype "passive"))
      (node (ref "UART2") (pin "4") (pinfunction "4_4") (pintype "passive"))
      (node (ref "UART3") (pin "4") (pinfunction "4_4") (pintype "passive"))
      (node (ref "UART4") (pin "4") (pinfunction "4_4") (pintype "passive"))
      (node (ref "UART5") (pin "4") (pinfunction "4_4") (pintype "passive"))
      (node (ref "UART6") (pin "4") (pinfunction "4_4") (pintype "passive"))
    )
    (net (code "94") (name "unconnected-(LEFT-Pad48)") (class "Default")
      (node (ref "LEFT") (pin "48") (pinfunction "48_48") (pintype "passive"))
    )
  )
)
